# SparkX_smol_Header.net
KiCad netlist of a schematic drawn in EAGLE
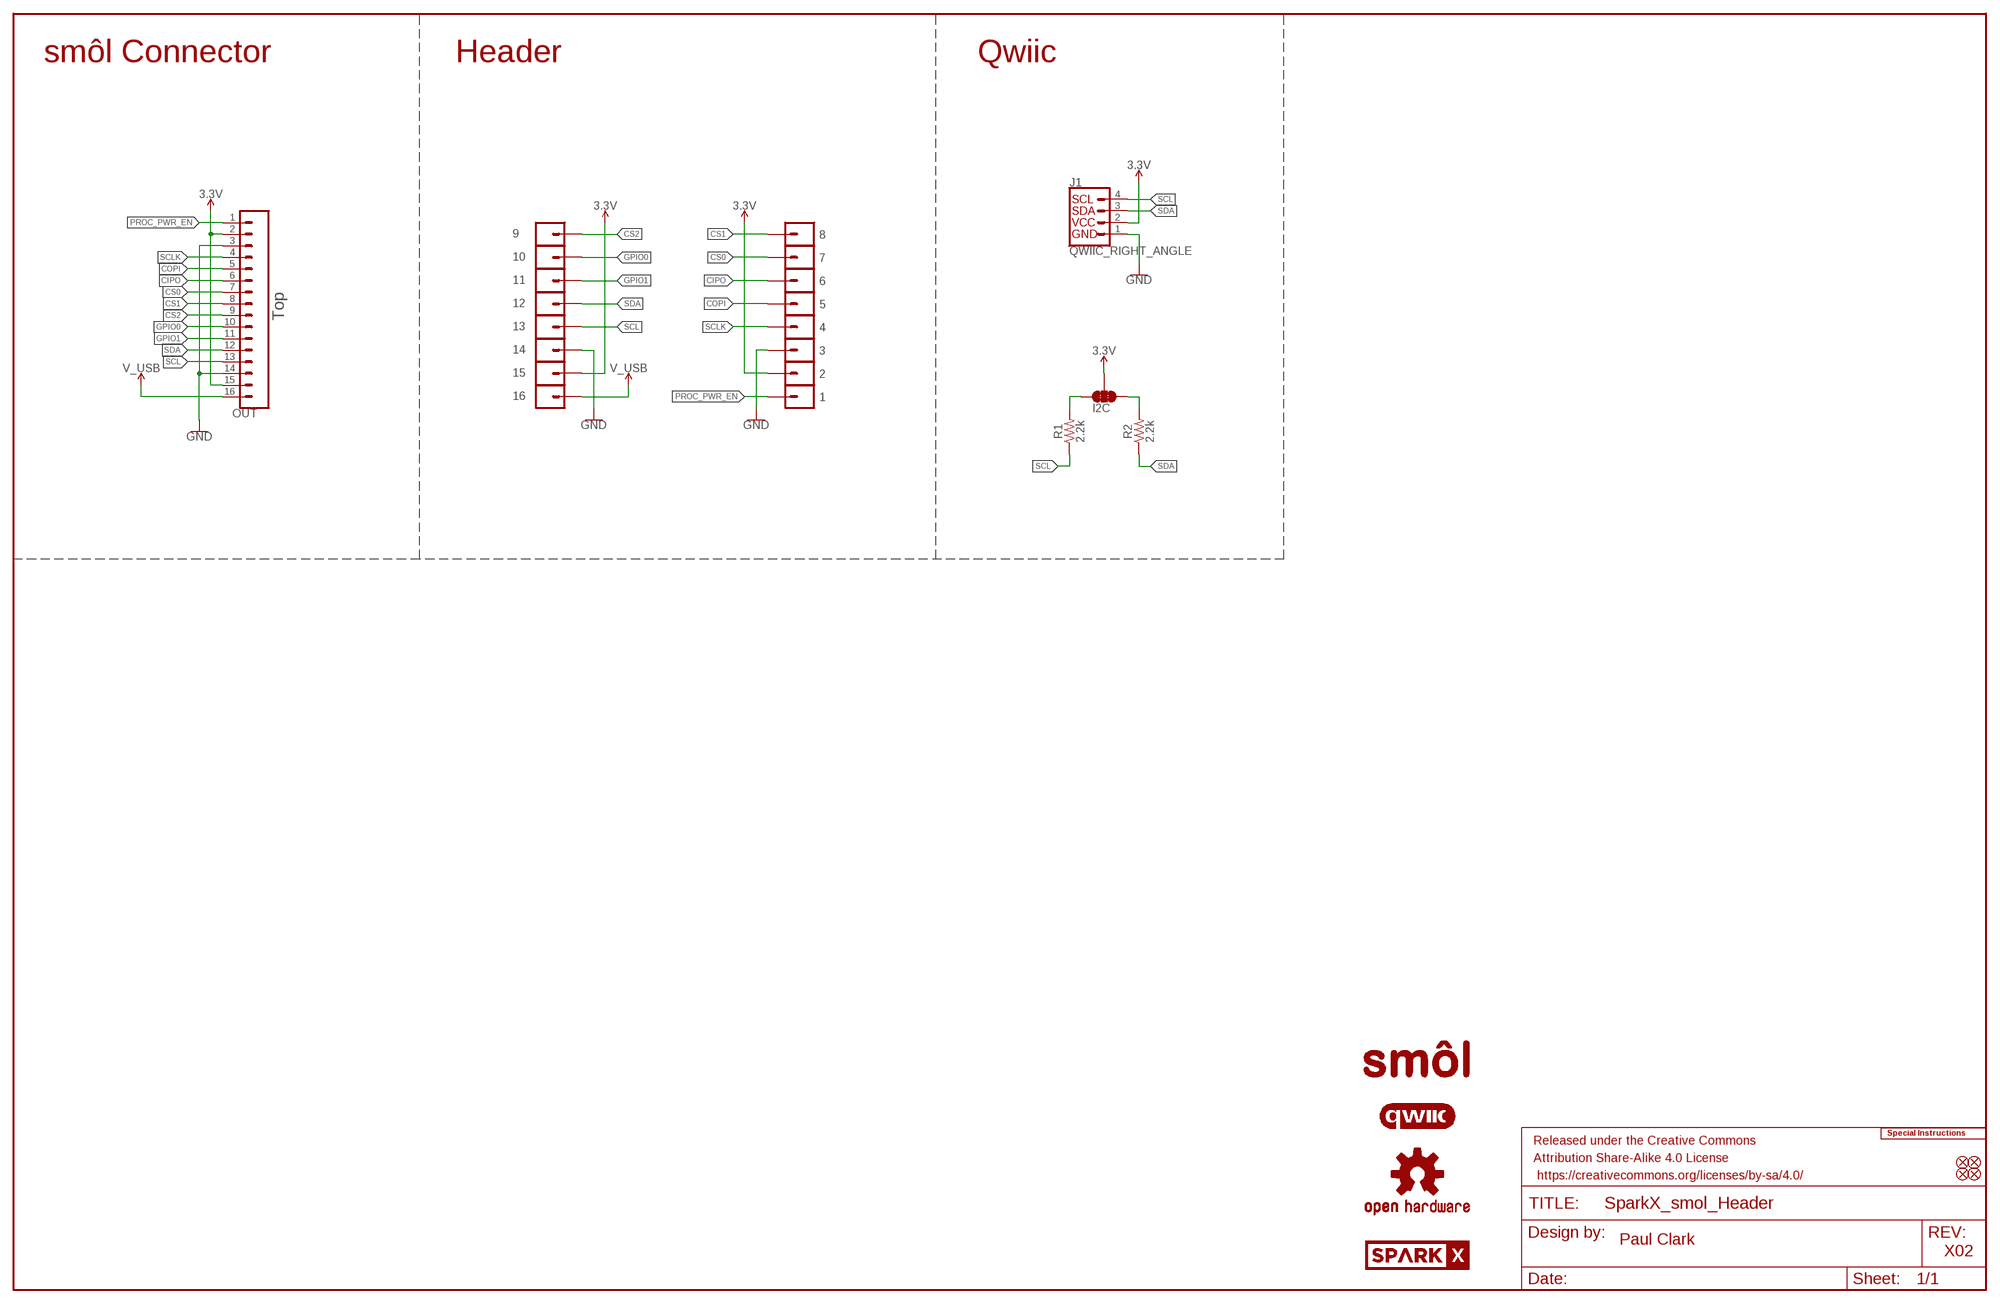
[diagram p0: schematic, sheet 1]

(export (version "E")
  (design (tool "Eeschema 10.0.6"))
  (components
    (comp (ref "1")
      (value "CONN_01PTH_NO_SILK_YES_STOP")
      (footprint "eagle-import:1X01_NO_SILK")
      (libsource (lib "eagle-import") (part "CONN_01PTH_NO_SILK_YES_STOP"))
    )
    (comp (ref "2")
      (value "CONN_01PTH_NO_SILK_YES_STOP")
      (footprint "eagle-import:1X01_NO_SILK")
      (libsource (lib "eagle-import") (part "CONN_01PTH_NO_SILK_YES_STOP"))
    )
    (comp (ref "3")
      (value "CONN_01PTH_NO_SILK_YES_STOP")
      (footprint "eagle-import:1X01_NO_SILK")
      (libsource (lib "eagle-import") (part "CONN_01PTH_NO_SILK_YES_STOP"))
    )
    (comp (ref "4")
      (value "CONN_01PTH_NO_SILK_YES_STOP")
      (footprint "eagle-import:1X01_NO_SILK")
      (libsource (lib "eagle-import") (part "CONN_01PTH_NO_SILK_YES_STOP"))
    )
    (comp (ref "5")
      (value "CONN_01PTH_NO_SILK_YES_STOP")
      (footprint "eagle-import:1X01_NO_SILK")
      (libsource (lib "eagle-import") (part "CONN_01PTH_NO_SILK_YES_STOP"))
    )
    (comp (ref "6")
      (value "CONN_01PTH_NO_SILK_YES_STOP")
      (footprint "eagle-import:1X01_NO_SILK")
      (libsource (lib "eagle-import") (part "CONN_01PTH_NO_SILK_YES_STOP"))
    )
    (comp (ref "7")
      (value "CONN_01PTH_NO_SILK_YES_STOP")
      (footprint "eagle-import:1X01_NO_SILK")
      (libsource (lib "eagle-import") (part "CONN_01PTH_NO_SILK_YES_STOP"))
    )
    (comp (ref "8")
      (value "CONN_01PTH_NO_SILK_YES_STOP")
      (footprint "eagle-import:1X01_NO_SILK")
      (libsource (lib "eagle-import") (part "CONN_01PTH_NO_SILK_YES_STOP"))
    )
    (comp (ref "9")
      (value "CONN_01PTH_NO_SILK_YES_STOP")
      (footprint "eagle-import:1X01_NO_SILK")
      (libsource (lib "eagle-import") (part "CONN_01PTH_NO_SILK_YES_STOP"))
    )
    (comp (ref "10")
      (value "CONN_01PTH_NO_SILK_YES_STOP")
      (footprint "eagle-import:1X01_NO_SILK")
      (libsource (lib "eagle-import") (part "CONN_01PTH_NO_SILK_YES_STOP"))
    )
    (comp (ref "11")
      (value "CONN_01PTH_NO_SILK_YES_STOP")
      (footprint "eagle-import:1X01_NO_SILK")
      (libsource (lib "eagle-import") (part "CONN_01PTH_NO_SILK_YES_STOP"))
    )
    (comp (ref "12")
      (value "CONN_01PTH_NO_SILK_YES_STOP")
      (footprint "eagle-import:1X01_NO_SILK")
      (libsource (lib "eagle-import") (part "CONN_01PTH_NO_SILK_YES_STOP"))
    )
    (comp (ref "13")
      (value "CONN_01PTH_NO_SILK_YES_STOP")
      (footprint "eagle-import:1X01_NO_SILK")
      (libsource (lib "eagle-import") (part "CONN_01PTH_NO_SILK_YES_STOP"))
    )
    (comp (ref "14")
      (value "CONN_01PTH_NO_SILK_YES_STOP")
      (footprint "eagle-import:1X01_NO_SILK")
      (libsource (lib "eagle-import") (part "CONN_01PTH_NO_SILK_YES_STOP"))
    )
    (comp (ref "15")
      (value "CONN_01PTH_NO_SILK_YES_STOP")
      (footprint "eagle-import:1X01_NO_SILK")
      (libsource (lib "eagle-import") (part "CONN_01PTH_NO_SILK_YES_STOP"))
    )
    (comp (ref "16")
      (value "CONN_01PTH_NO_SILK_YES_STOP")
      (footprint "eagle-import:1X01_NO_SILK")
      (libsource (lib "eagle-import") (part "CONN_01PTH_NO_SILK_YES_STOP"))
    )
    (comp (ref "FD1")
      (value "FIDUCIALUFIDUCIAL")
      (footprint "eagle-import:FIDUCIAL-MICRO")
      (libsource (lib "eagle-import") (part "FIDUCIALUFIDUCIAL"))
    )
    (comp (ref "FD2")
      (value "FIDUCIALUFIDUCIAL")
      (footprint "eagle-import:FIDUCIAL-MICRO")
      (libsource (lib "eagle-import") (part "FIDUCIALUFIDUCIAL"))
    )
    (comp (ref "FD3")
      (value "FIDUCIALUFIDUCIAL")
      (footprint "eagle-import:FIDUCIAL-MICRO")
      (libsource (lib "eagle-import") (part "FIDUCIALUFIDUCIAL"))
    )
    (comp (ref "FD4")
      (value "FIDUCIALUFIDUCIAL")
      (footprint "eagle-import:FIDUCIAL-MICRO")
      (libsource (lib "eagle-import") (part "FIDUCIALUFIDUCIAL"))
    )
    (comp (ref "FRAME1")
      (value "FRAME-LEDGER")
      (footprint "eagle-import:CREATIVE_COMMONS")
      (libsource (lib "eagle-import") (part "FRAME-LEDGER"))
    )
    (comp (ref "I2C")
      (value "JUMPER-SMT_3_2-NC_TRACE_SILK")
      (footprint "eagle-import:SMT-JUMPER_3_2-NC_TRACE_SILK")
      (libsource (lib "eagle-import") (part "JUMPER-SMT_3_2-NC_TRACE_SILK"))
    )
    (comp (ref "J1")
      (value "QWIIC_RIGHT_ANGLE")
      (footprint "eagle-import:JST04_1MM_RA")
      (libsource (lib "eagle-import") (part "QWIIC_CONNECTORJS-1MM"))
    )
    (comp (ref "LOGO1")
      (value "SPECIAL_INSTRUCTIONS-ORDERING")
      (footprint "eagle-import:ORDERING_INSTRUCTIONS")
      (libsource (lib "eagle-import") (part "SPECIAL_INSTRUCTIONS-ORDERING"))
    )
    (comp (ref "LOGO2")
      (value "OSHW-LOGOMINI")
      (footprint "eagle-import:OSHW-LOGO-MINI")
      (libsource (lib "eagle-import") (part "OSHW-LOGOMINI"))
    )
    (comp (ref "LOGO3")
      (value "OSHW-LOGOMINI")
      (footprint "eagle-import:OSHW-LOGO-MINI")
      (libsource (lib "eagle-import") (part "OSHW-LOGOMINI"))
    )
    (comp (ref "LOGO4")
      (value "QWIIC_LOGO_5MM")
      (footprint "eagle-import:QWIIC_5MM")
      (libsource (lib "eagle-import") (part "QWIIC_LOGO_5MM"))
    )
    (comp (ref "OUT")
      (value "CONN_16FPC_16_0.5MM")
      (footprint "eagle-import:FPC_16_0.5MM")
      (libsource (lib "eagle-import") (part "CONN_16FPC_16_0.5MM"))
    )
    (comp (ref "R1")
      (value "2.2k")
      (footprint "eagle-import:0603")
      (libsource (lib "eagle-import") (part "2.2KOHM-0603-1/10W-1%"))
    )
    (comp (ref "R2")
      (value "2.2k")
      (footprint "eagle-import:0603")
      (libsource (lib "eagle-import") (part "2.2KOHM-0603-1/10W-1%"))
    )
    (comp (ref "U$1")
      (value "SPARKX-LOGO3")
      (footprint "eagle-import:SPARKX-SMALL")
      (libsource (lib "eagle-import") (part "SPARKX-LOGO3"))
    )
    (comp (ref "U$39")
      (value "SMOL_LOGOSMALL")
      (footprint "eagle-import:SMOL_SMALL")
      (libsource (lib "eagle-import") (part "SMOL_LOGOSMALL"))
    )
  )
  (nets
    (net (code "1") (name "3.3V") (class "Default")
      (node (ref "15") (pin "1") (pinfunction "1_1") (pintype "passive"))
      (node (ref "2") (pin "1") (pinfunction "1_1") (pintype "passive"))
      (node (ref "I2C") (pin "2") (pinfunction "2_2") (pintype "passive"))
      (node (ref "J1") (pin "2") (pinfunction "2_2") (pintype "power_in"))
      (node (ref "OUT") (pin "15") (pinfunction "15_15") (pintype "passive"))
      (node (ref "OUT") (pin "2") (pinfunction "2_2") (pintype "passive"))
    )
    (net (code "2") (name "CIPO") (class "Default")
      (node (ref "6") (pin "1") (pinfunction "1_1") (pintype "passive"))
      (node (ref "OUT") (pin "6") (pinfunction "6_6") (pintype "passive"))
    )
    (net (code "3") (name "COPI") (class "Default")
      (node (ref "5") (pin "1") (pinfunction "1_1") (pintype "passive"))
      (node (ref "OUT") (pin "5") (pinfunction "5_5") (pintype "passive"))
    )
    (net (code "4") (name "CS0") (class "Default")
      (node (ref "7") (pin "1") (pinfunction "1_1") (pintype "passive"))
      (node (ref "OUT") (pin "7") (pinfunction "7_7") (pintype "passive"))
    )
    (net (code "5") (name "CS1") (class "Default")
      (node (ref "8") (pin "1") (pinfunction "1_1") (pintype "passive"))
      (node (ref "OUT") (pin "8") (pinfunction "8_8") (pintype "passive"))
    )
    (net (code "6") (name "CS2") (class "Default")
      (node (ref "9") (pin "1") (pinfunction "1_1") (pintype "passive"))
      (node (ref "OUT") (pin "9") (pinfunction "9_9") (pintype "passive"))
    )
    (net (code "7") (name "GND") (class "Default")
      (node (ref "14") (pin "1") (pinfunction "1_1") (pintype "passive"))
      (node (ref "3") (pin "1") (pinfunction "1_1") (pintype "passive"))
      (node (ref "J1") (pin "1") (pinfunction "1_1") (pintype "power_in"))
      (node (ref "OUT") (pin "14") (pinfunction "14_14") (pintype "passive"))
      (node (ref "OUT") (pin "3") (pinfunction "3_3") (pintype "passive"))
    )
    (net (code "8") (name "GPIO0") (class "Default")
      (node (ref "10") (pin "1") (pinfunction "1_1") (pintype "passive"))
      (node (ref "OUT") (pin "10") (pinfunction "10_10") (pintype "passive"))
    )
    (net (code "9") (name "GPIO1") (class "Default")
      (node (ref "11") (pin "1") (pinfunction "1_1") (pintype "passive"))
      (node (ref "OUT") (pin "11") (pinfunction "11_11") (pintype "passive"))
    )
    (net (code "10") (name "Net-(I2C-Pad1)") (class "Default")
      (node (ref "I2C") (pin "1") (pinfunction "1_1") (pintype "passive"))
      (node (ref "R2") (pin "2") (pinfunction "2_2") (pintype "passive"))
    )
    (net (code "11") (name "Net-(I2C-Pad3)") (class "Default")
      (node (ref "I2C") (pin "3") (pinfunction "3_3") (pintype "passive"))
      (node (ref "R1") (pin "2") (pinfunction "2_2") (pintype "passive"))
    )
    (net (code "12") (name "PROC_PWR_EN") (class "Default")
      (node (ref "1") (pin "1") (pinfunction "1_1") (pintype "passive"))
      (node (ref "OUT") (pin "1") (pinfunction "1_1") (pintype "passive"))
    )
    (net (code "13") (name "SCL") (class "Default")
      (node (ref "13") (pin "1") (pinfunction "1_1") (pintype "passive"))
      (node (ref "J1") (pin "4") (pinfunction "4_4") (pintype "passive"))
      (node (ref "OUT") (pin "13") (pinfunction "13_13") (pintype "passive"))
      (node (ref "R1") (pin "1") (pinfunction "1_1") (pintype "passive"))
    )
    (net (code "14") (name "SCLK") (class "Default")
      (node (ref "4") (pin "1") (pinfunction "1_1") (pintype "passive"))
      (node (ref "OUT") (pin "4") (pinfunction "4_4") (pintype "passive"))
    )
    (net (code "15") (name "SDA") (class "Default")
      (node (ref "12") (pin "1") (pinfunction "1_1") (pintype "passive"))
      (node (ref "J1") (pin "3") (pinfunction "3_3") (pintype "passive"))
      (node (ref "OUT") (pin "12") (pinfunction "12_12") (pintype "passive"))
      (node (ref "R2") (pin "1") (pinfunction "1_1") (pintype "passive"))
    )
    (net (code "16") (name "V_USB") (class "Default")
      (node (ref "16") (pin "1") (pinfunction "1_1") (pintype "passive"))
      (node (ref "OUT") (pin "16") (pinfunction "16_16") (pintype "passive"))
    )
  )
)
